# bandpass_filter.net
KiCad netlist of a schematic drawn in Altium Designer
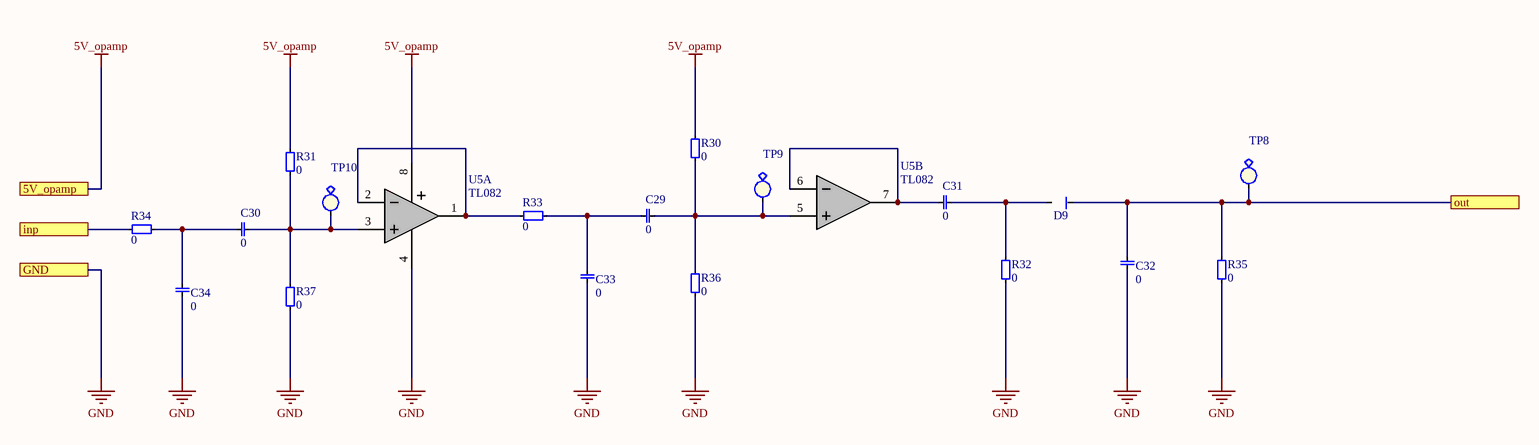
[diagram p0: bandpass_filter.schdoc]

(export (version "E")
  (design (tool "Eeschema 10.0.6"))
  (components
    (comp (ref "C29")
      (value "0")
      (footprint "1206, capasitor")
      (fields (field (name "Comment") "1206, capacitor"))
      (libsource (lib "jclib") (part "1206, capacitor"))
    )
    (comp (ref "C30")
      (value "0")
      (footprint "1206, capasitor")
      (fields (field (name "Comment") "1206, capacitor"))
      (libsource (lib "jclib") (part "1206, capacitor"))
    )
    (comp (ref "C31")
      (value "0")
      (footprint "1206, capasitor")
      (fields (field (name "Comment") "1206, capacitor"))
      (libsource (lib "jclib") (part "1206, capacitor"))
    )
    (comp (ref "C32")
      (value "0")
      (footprint "1206, capasitor")
      (fields (field (name "Comment") "1206, capacitor"))
      (libsource (lib "jclib") (part "1206, capacitor"))
    )
    (comp (ref "C33")
      (value "0")
      (footprint "1206, capasitor")
      (fields (field (name "Comment") "1206, capacitor"))
      (libsource (lib "jclib") (part "1206, capacitor"))
    )
    (comp (ref "C34")
      (value "0")
      (footprint "1206, capasitor")
      (fields (field (name "Comment") "1206, capacitor"))
      (libsource (lib "jclib") (part "1206, capacitor"))
    )
    (comp (ref "D9") (value "Diode, TH") (footprint "TO-220-F2") (libsource (lib "jclib") (part "Diode, TH")))
    (comp (ref "R30")
      (value "0")
      (footprint "1206")
      (description "Resistor")
      (fields (field (name "Comment") "1206, resistor"))
      (libsource (lib "jclib") (part "1206, resistor"))
    )
    (comp (ref "R31")
      (value "0")
      (footprint "1206")
      (description "Resistor")
      (fields (field (name "Comment") "1206, resistor"))
      (libsource (lib "jclib") (part "1206, resistor"))
    )
    (comp (ref "R32")
      (value "0")
      (footprint "1206")
      (description "Resistor")
      (fields (field (name "Comment") "1206, resistor"))
      (libsource (lib "jclib") (part "1206, resistor"))
    )
    (comp (ref "R33")
      (value "0")
      (footprint "1206")
      (description "Resistor")
      (fields (field (name "Comment") "1206, resistor"))
      (libsource (lib "jclib") (part "1206, resistor"))
    )
    (comp (ref "R34")
      (value "0")
      (footprint "1206")
      (description "Resistor")
      (fields (field (name "Comment") "1206, resistor"))
      (libsource (lib "jclib") (part "1206, resistor"))
    )
    (comp (ref "R35")
      (value "0")
      (footprint "1206")
      (description "Resistor")
      (fields (field (name "Comment") "1206, resistor"))
      (libsource (lib "jclib") (part "1206, resistor"))
    )
    (comp (ref "R36")
      (value "0")
      (footprint "1206")
      (description "Resistor")
      (fields (field (name "Comment") "1206, resistor"))
      (libsource (lib "jclib") (part "1206, resistor"))
    )
    (comp (ref "R37")
      (value "0")
      (footprint "1206")
      (description "Resistor")
      (fields (field (name "Comment") "1206, resistor"))
      (libsource (lib "jclib") (part "1206, resistor"))
    )
    (comp (ref "TP8")
      (value "Test Point")
      (footprint "testPoint")
      (libsource (lib "jclib") (part "Test Point"))
    )
    (comp (ref "TP9")
      (value "Test Point")
      (footprint "testPoint")
      (libsource (lib "jclib") (part "Test Point"))
    )
    (comp (ref "TP10")
      (value "Test Point")
      (footprint "testPoint")
      (libsource (lib "jclib") (part "Test Point"))
    )
    (comp (ref "U5")
      (value "TL082")
      (footprint "SOIC8")
      (description "Dual FET-Input Operational Amplifier")
      (libsource (lib "jclib") (part "TL082"))
    )
  )
  (nets
    (net (code "1") (name "/inp") (class "Default")
      (node (ref "R34") (pin "1") (pinfunction "1_1") (pintype "passive"))
    )
    (net (code "2") (name "/out") (class "Default")
      (node (ref "C32") (pin "1") (pinfunction "1_1") (pintype "passive"))
      (node (ref "D9") (pin "1") (pinfunction "1_1") (pintype "passive"))
      (node (ref "R35") (pin "0") (pinfunction "0_0") (pintype "passive"))
      (node (ref "TP8") (pin "0") (pinfunction "0_0") (pintype "passive"))
    )
    (net (code "3") (name "5V_opamp") (class "Default")
      (node (ref "R30") (pin "0") (pinfunction "0_0") (pintype "passive"))
      (node (ref "R31") (pin "0") (pinfunction "0_0") (pintype "passive"))
      (node (ref "U5") (pin "8") (pinfunction "V+_8") (pintype "passive"))
    )
    (net (code "4") (name "GND") (class "Default")
      (node (ref "C32") (pin "0") (pinfunction "0_0") (pintype "passive"))
      (node (ref "C33") (pin "0") (pinfunction "0_0") (pintype "passive"))
      (node (ref "C34") (pin "0") (pinfunction "0_0") (pintype "passive"))
      (node (ref "R32") (pin "1") (pinfunction "1_1") (pintype "passive"))
      (node (ref "R35") (pin "1") (pinfunction "1_1") (pintype "passive"))
      (node (ref "R36") (pin "1") (pinfunction "1_1") (pintype "passive"))
      (node (ref "R37") (pin "1") (pinfunction "1_1") (pintype "passive"))
      (node (ref "U5") (pin "4") (pinfunction "V-_4") (pintype "passive"))
    )
    (net (code "5") (name "Net-(C29-Pad1)") (class "Default")
      (node (ref "C29") (pin "1") (pinfunction "1_1") (pintype "passive"))
      (node (ref "C33") (pin "1") (pinfunction "1_1") (pintype "passive"))
      (node (ref "R33") (pin "0") (pinfunction "0_0") (pintype "passive"))
    )
    (net (code "6") (name "Net-(C30-Pad1)") (class "Default")
      (node (ref "C30") (pin "1") (pinfunction "1_1") (pintype "passive"))
      (node (ref "C34") (pin "1") (pinfunction "1_1") (pintype "passive"))
      (node (ref "R34") (pin "0") (pinfunction "0_0") (pintype "passive"))
    )
    (net (code "7") (name "Net-(C31-Pad0)") (class "Default")
      (node (ref "C31") (pin "0") (pinfunction "0_0") (pintype "passive"))
      (node (ref "D9") (pin "2") (pinfunction "2_2") (pintype "passive"))
      (node (ref "R32") (pin "0") (pinfunction "0_0") (pintype "passive"))
    )
    (net (code "8") (name "Net-(U5A-IN+)") (class "Default")
      (node (ref "C30") (pin "0") (pinfunction "0_0") (pintype "passive"))
      (node (ref "R31") (pin "1") (pinfunction "1_1") (pintype "passive"))
      (node (ref "R37") (pin "0") (pinfunction "0_0") (pintype "passive"))
      (node (ref "TP10") (pin "0") (pinfunction "0_0") (pintype "passive"))
      (node (ref "U5") (pin "3") (pinfunction "IN+_3") (pintype "passive"))
    )
    (net (code "9") (name "Net-(U5A-IN-)") (class "Default")
      (node (ref "R33") (pin "1") (pinfunction "1_1") (pintype "passive"))
      (node (ref "U5") (pin "1") (pinfunction "OUT1_1") (pintype "passive"))
      (node (ref "U5") (pin "2") (pinfunction "IN-_2") (pintype "passive"))
    )
    (net (code "10") (name "Net-(U5B-IN+)") (class "Default")
      (node (ref "C29") (pin "0") (pinfunction "0_0") (pintype "passive"))
      (node (ref "R30") (pin "1") (pinfunction "1_1") (pintype "passive"))
      (node (ref "R36") (pin "0") (pinfunction "0_0") (pintype "passive"))
      (node (ref "TP9") (pin "0") (pinfunction "0_0") (pintype "passive"))
      (node (ref "U5") (pin "5") (pinfunction "IN+_5") (pintype "passive"))
    )
    (net (code "11") (name "Net-(U5B-IN-)") (class "Default")
      (node (ref "C31") (pin "1") (pinfunction "1_1") (pintype "passive"))
      (node (ref "U5") (pin "6") (pinfunction "IN-_6") (pintype "passive"))
      (node (ref "U5") (pin "7") (pinfunction "OUT2_7") (pintype "passive"))
    )
  )
)
